# -.net
KiCad netlist of a schematic drawn in Altium Designer
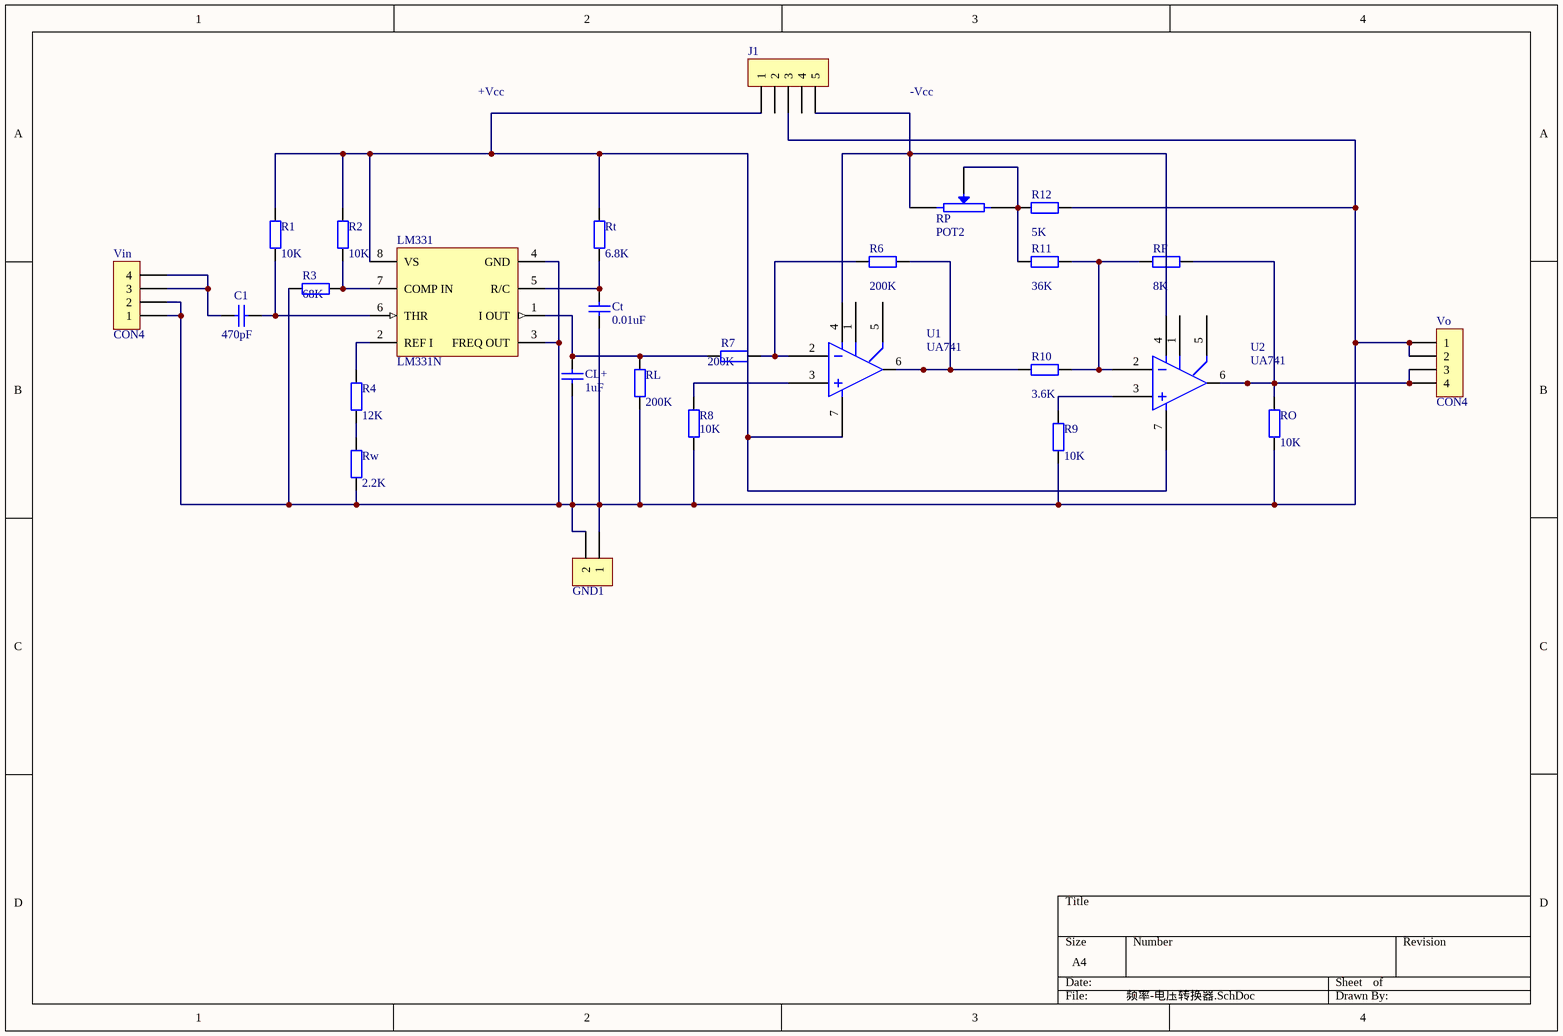
[diagram p0: 频率-电压转换器.SchDoc]

(export (version "E")
  (design (tool "Eeschema 10.0.6"))
  (components
    (comp (ref "C1")
      (value "470pF")
      (footprint "RAD-0.2")
      (description "Capacitor")
      (fields (field (name "Comment") "Cap") (field (name "PUBLISHER") "Altium Limited"))
      (libsource (lib "Miscellaneous Devices") (part "Cap"))
    )
    (comp (ref "CL+")
      (value "1uF")
      (footprint "RAD-0.2")
      (description "Capacitor")
      (fields (field (name "Comment") "Cap") (field (name "PUBLISHER") "Altium Limited"))
      (libsource (lib "Miscellaneous Devices") (part "Cap"))
    )
    (comp (ref "Ct")
      (value "0.01uF")
      (footprint "RAD-0.2")
      (description "Capacitor")
      (fields (field (name "Comment") "Cap") (field (name "PUBLISHER") "Altium Limited"))
      (libsource (lib "Miscellaneous Devices") (part "Cap"))
    )
    (comp (ref "GND1")
      (value "CON2")
      (footprint "SIP-2")
      (description "Connector")
      (libsource (lib "Miscellaneous Devices") (part "CON2"))
    )
    (comp (ref "J1")
      (value "CON5")
      (footprint "POWER PLUG5")
      (description "Connector")
      (libsource (lib "Miscellaneous Devices") (part "CON5"))
    )
    (comp (ref "LM331")
      (value "LM331N")
      (footprint "N08E")
      (description "Precision Voltage-to-Frequency Converters, 8-pin MDIP")
      (fields
        (field (name "MANUFACTURER") "National Semiconductor")
        (field (name "PUBLISHER") "Altium Limited")
      )
      (libsource (lib "NSC Analog") (part "LM331N"))
    )
    (comp (ref "R1")
      (value "10K")
      (footprint "AXIAL-0.4")
      (description "Resistor")
      (fields (field (name "Comment") "Res2") (field (name "PUBLISHER") "Altium Limited"))
      (libsource (lib "") (part "Res2_1"))
    )
    (comp (ref "R2")
      (value "10K")
      (footprint "AXIAL-0.4")
      (description "Resistor")
      (fields (field (name "Comment") "Res2") (field (name "PUBLISHER") "Altium Limited"))
      (libsource (lib "") (part "Res2_1"))
    )
    (comp (ref "R3")
      (value "68K")
      (footprint "AXIAL-0.4")
      (description "Resistor")
      (fields (field (name "Comment") "Res2") (field (name "PUBLISHER") "Altium Limited"))
      (libsource (lib "Miscellaneous Devices") (part "Res2"))
    )
    (comp (ref "R4")
      (value "12K")
      (footprint "AXIAL-0.4")
      (description "Resistor")
      (fields (field (name "Comment") "Res2") (field (name "PUBLISHER") "Altium Limited"))
      (libsource (lib "") (part "Res2_1"))
    )
    (comp (ref "R6")
      (value "200K")
      (footprint "AXIAL-0.4")
      (description "Resistor")
      (fields (field (name "Comment") "Res2") (field (name "PUBLISHER") "Altium Limited"))
      (libsource (lib "") (part "Res2_2"))
    )
    (comp (ref "R7")
      (value "200K")
      (footprint "AXIAL-0.4")
      (description "Resistor")
      (fields (field (name "Comment") "Res2") (field (name "PUBLISHER") "Altium Limited"))
      (libsource (lib "") (part "Res2_2"))
    )
    (comp (ref "R8")
      (value "10K")
      (footprint "AXIAL-0.4")
      (description "Resistor")
      (fields (field (name "Comment") "Res2") (field (name "PUBLISHER") "Altium Limited"))
      (libsource (lib "") (part "Res2_3"))
    )
    (comp (ref "R9")
      (value "10K")
      (footprint "AXIAL-0.4")
      (description "Resistor")
      (fields (field (name "Comment") "Res2") (field (name "PUBLISHER") "Altium Limited"))
      (libsource (lib "") (part "Res2_1"))
    )
    (comp (ref "R10")
      (value "3.6K")
      (footprint "AXIAL-0.4")
      (description "Resistor")
      (fields (field (name "Comment") "Res2") (field (name "PUBLISHER") "Altium Limited"))
      (libsource (lib "") (part "Res2_2"))
    )
    (comp (ref "R11")
      (value "36K")
      (footprint "AXIAL-0.4")
      (description "Resistor")
      (fields (field (name "Comment") "Res2") (field (name "PUBLISHER") "Altium Limited"))
      (libsource (lib "") (part "Res2_2"))
    )
    (comp (ref "R12")
      (value "5K")
      (footprint "AXIAL-0.4")
      (description "Resistor")
      (fields (field (name "Comment") "Res2") (field (name "PUBLISHER") "Altium Limited"))
      (libsource (lib "") (part "Res2_2"))
    )
    (comp (ref "RF")
      (value "8K")
      (footprint "AXIAL-0.4")
      (description "Resistor")
      (fields (field (name "Comment") "Res2") (field (name "PUBLISHER") "Altium Limited"))
      (libsource (lib "") (part "Res2_2"))
    )
    (comp (ref "RL")
      (value "200K")
      (footprint "AXIAL-0.4")
      (description "Resistor")
      (fields (field (name "Comment") "Res2") (field (name "PUBLISHER") "Altium Limited"))
      (libsource (lib "") (part "Res2_1"))
    )
    (comp (ref "RO")
      (value "10K")
      (footprint "AXIAL-0.4")
      (description "Resistor")
      (fields (field (name "Comment") "Res2") (field (name "PUBLISHER") "Altium Limited"))
      (libsource (lib "") (part "Res2_3"))
    )
    (comp (ref "RP")
      (value "POT2")
      (footprint "RP3296")
      (description "Potentiometer")
      (libsource (lib "Miscellaneous Devices") (part "POT2"))
    )
    (comp (ref "Rt")
      (value "6.8K")
      (footprint "AXIAL-0.4")
      (description "Resistor")
      (fields (field (name "Comment") "Res2") (field (name "PUBLISHER") "Altium Limited"))
      (libsource (lib "") (part "Res2_1"))
    )
    (comp (ref "Rw")
      (value "2.2K")
      (footprint "AXIAL-0.4")
      (description "Resistor")
      (fields (field (name "Comment") "Res2") (field (name "PUBLISHER") "Altium Limited"))
      (libsource (lib "") (part "Res2_1"))
    )
    (comp (ref "U1")
      (value "UA741")
      (footprint "DIP-8")
      (libsource (lib "Schematic Operational Amplifiers") (part "UA741"))
    )
    (comp (ref "U2")
      (value "UA741")
      (footprint "DIP-8")
      (libsource (lib "Schematic Operational Amplifiers") (part "UA741"))
    )
    (comp (ref "Vin")
      (value "CON4")
      (footprint "SIP-4")
      (description "Connector")
      (libsource (lib "Miscellaneous Devices") (part "CON4"))
    )
    (comp (ref "Vo")
      (value "CON4")
      (footprint "SIP-4")
      (description "Connector")
      (libsource (lib "") (part "CON4_1"))
    )
  )
  (nets
    (net (code "1") (name "Net-(C1-Pad1)") (class "Default")
      (node (ref "C1") (pin "1") (pinfunction "1_1") (pintype "passive"))
      (node (ref "Vin") (pin "3") (pinfunction "3_3") (pintype "passive"))
      (node (ref "Vin") (pin "4") (pinfunction "4_4") (pintype "passive"))
    )
    (net (code "2") (name "Net-(J1-Pad5)") (class "Default")
      (node (ref "J1") (pin "5") (pinfunction "5_5") (pintype "passive"))
      (node (ref "RP") (pin "1") (pinfunction "1_1") (pintype "passive"))
      (node (ref "U1") (pin "4") (pintype "passive"))
      (node (ref "U2") (pin "4") (pintype "passive"))
    )
    (net (code "3") (name "Net-(LM331-COMP_IN)") (class "Default")
      (node (ref "LM331") (pin "7") (pinfunction "COMP_IN_7") (pintype "passive"))
      (node (ref "R2") (pin "1") (pinfunction "1_1") (pintype "passive"))
      (node (ref "R3") (pin "2") (pinfunction "2_2") (pintype "passive"))
    )
    (net (code "4") (name "Net-(LM331-FREQ_OUT)") (class "Default")
      (node (ref "CL+") (pin "1") (pinfunction "1_1") (pintype "passive"))
      (node (ref "Ct") (pin "1") (pinfunction "1_1") (pintype "passive"))
      (node (ref "GND1") (pin "1") (pinfunction "1_1") (pintype "passive"))
      (node (ref "GND1") (pin "2") (pinfunction "2_2") (pintype "passive"))
      (node (ref "J1") (pin "3") (pinfunction "3_3") (pintype "passive"))
      (node (ref "LM331") (pin "3") (pinfunction "FREQ_OUT_3") (pintype "passive"))
      (node (ref "LM331") (pin "4") (pinfunction "GND_4") (pintype "passive"))
      (node (ref "R12") (pin "1") (pinfunction "1_1") (pintype "passive"))
      (node (ref "R3") (pin "1") (pinfunction "1_1") (pintype "passive"))
      (node (ref "R8") (pin "2") (pinfunction "2_2") (pintype "passive"))
      (node (ref "R9") (pin "1") (pinfunction "1_1") (pintype "passive"))
      (node (ref "RL") (pin "1") (pinfunction "1_1") (pintype "passive"))
      (node (ref "RO") (pin "2") (pinfunction "2_2") (pintype "passive"))
      (node (ref "Rw") (pin "1") (pinfunction "1_1") (pintype "passive"))
      (node (ref "Vin") (pin "1") (pinfunction "1_1") (pintype "passive"))
      (node (ref "Vin") (pin "2") (pinfunction "2_2") (pintype "passive"))
      (node (ref "Vo") (pin "1") (pinfunction "1_1") (pintype "passive"))
      (node (ref "Vo") (pin "2") (pinfunction "2_2") (pintype "passive"))
    )
    (net (code "5") (name "Net-(LM331-I_OUT)") (class "Default")
      (node (ref "CL+") (pin "2") (pinfunction "2_2") (pintype "passive"))
      (node (ref "LM331") (pin "1") (pinfunction "I_OUT_1") (pintype "output"))
      (node (ref "R7") (pin "2") (pinfunction "2_2") (pintype "passive"))
      (node (ref "RL") (pin "2") (pinfunction "2_2") (pintype "passive"))
    )
    (net (code "6") (name "Net-(LM331-REF_I)") (class "Default")
      (node (ref "LM331") (pin "2") (pinfunction "REF_I_2") (pintype "passive"))
      (node (ref "R4") (pin "2") (pinfunction "2_2") (pintype "passive"))
    )
    (net (code "7") (name "Net-(LM331-R{slash}C)") (class "Default")
      (node (ref "Ct") (pin "2") (pinfunction "2_2") (pintype "passive"))
      (node (ref "LM331") (pin "5") (pinfunction "R/C_5") (pintype "passive"))
      (node (ref "Rt") (pin "1") (pinfunction "1_1") (pintype "passive"))
    )
    (net (code "8") (name "Net-(LM331-THR)") (class "Default")
      (node (ref "C1") (pin "2") (pinfunction "2_2") (pintype "passive"))
      (node (ref "LM331") (pin "6") (pinfunction "THR_6") (pintype "input"))
      (node (ref "R1") (pin "1") (pinfunction "1_1") (pintype "passive"))
    )
    (net (code "9") (name "Net-(LM331-VS)") (class "Default")
      (node (ref "J1") (pin "1") (pinfunction "1_1") (pintype "passive"))
      (node (ref "LM331") (pin "8") (pinfunction "VS_8") (pintype "power_in"))
      (node (ref "R1") (pin "2") (pinfunction "2_2") (pintype "passive"))
      (node (ref "R2") (pin "2") (pinfunction "2_2") (pintype "passive"))
      (node (ref "Rt") (pin "2") (pinfunction "2_2") (pintype "passive"))
      (node (ref "U1") (pin "7") (pintype "passive"))
      (node (ref "U2") (pin "7") (pintype "passive"))
    )
    (net (code "10") (name "Net-(R4-Pad1)") (class "Default")
      (node (ref "R4") (pin "1") (pinfunction "1_1") (pintype "passive"))
      (node (ref "Rw") (pin "2") (pinfunction "2_2") (pintype "passive"))
    )
    (net (code "11") (name "Net-(R6-Pad2)") (class "Default")
      (node (ref "R6") (pin "2") (pinfunction "2_2") (pintype "passive"))
      (node (ref "R7") (pin "1") (pinfunction "1_1") (pintype "passive"))
      (node (ref "U1") (pin "2") (pintype "passive"))
    )
    (net (code "12") (name "Net-(R8-Pad1)") (class "Default")
      (node (ref "R8") (pin "1") (pinfunction "1_1") (pintype "passive"))
      (node (ref "U1") (pin "3") (pintype "passive"))
    )
    (net (code "13") (name "Net-(R9-Pad2)") (class "Default")
      (node (ref "R9") (pin "2") (pinfunction "2_2") (pintype "passive"))
      (node (ref "U2") (pin "3") (pintype "passive"))
    )
    (net (code "14") (name "Net-(R10-Pad1)") (class "Default")
      (node (ref "R10") (pin "1") (pinfunction "1_1") (pintype "passive"))
      (node (ref "R11") (pin "1") (pinfunction "1_1") (pintype "passive"))
      (node (ref "RF") (pin "2") (pinfunction "2_2") (pintype "passive"))
      (node (ref "U2") (pin "2") (pintype "passive"))
    )
    (net (code "15") (name "Net-(R10-Pad2)") (class "Default")
      (node (ref "R10") (pin "2") (pinfunction "2_2") (pintype "passive"))
      (node (ref "R6") (pin "1") (pinfunction "1_1") (pintype "passive"))
      (node (ref "U1") (pin "6") (pintype "passive"))
    )
    (net (code "16") (name "Net-(RF-Pad1)") (class "Default")
      (node (ref "RF") (pin "1") (pinfunction "1_1") (pintype "passive"))
      (node (ref "RO") (pin "1") (pinfunction "1_1") (pintype "passive"))
      (node (ref "U2") (pin "6") (pintype "passive"))
      (node (ref "Vo") (pin "3") (pinfunction "3_3") (pintype "passive"))
      (node (ref "Vo") (pin "4") (pinfunction "4_4") (pintype "passive"))
    )
    (net (code "17") (name "Net-(RP-W)") (class "Default")
      (node (ref "R11") (pin "2") (pinfunction "2_2") (pintype "passive"))
      (node (ref "R12") (pin "2") (pinfunction "2_2") (pintype "passive"))
      (node (ref "RP") (pin "2") (pinfunction "2_2") (pintype "passive"))
      (node (ref "RP") (pin "3") (pinfunction "W_3") (pintype "passive"))
    )
    (net (code "18") (name "unconnected-(J1-Pad2)") (class "Default")
      (node (ref "J1") (pin "2") (pinfunction "2_2") (pintype "passive"))
    )
    (net (code "19") (name "unconnected-(J1-Pad4)") (class "Default")
      (node (ref "J1") (pin "4") (pinfunction "4_4") (pintype "passive"))
    )
    (net (code "20") (name "unconnected-(U1-Pad1)") (class "Default")
      (node (ref "U1") (pin "1") (pintype "passive"))
    )
    (net (code "21") (name "unconnected-(U1-Pad5)") (class "Default")
      (node (ref "U1") (pin "5") (pintype "passive"))
    )
    (net (code "22") (name "unconnected-(U2-Pad1)") (class "Default")
      (node (ref "U2") (pin "1") (pintype "passive"))
    )
    (net (code "23") (name "unconnected-(U2-Pad5)") (class "Default")
      (node (ref "U2") (pin "5") (pintype "passive"))
    )
  )
)
